# adc.net
KiCad netlist of a schematic drawn in Altium Designer
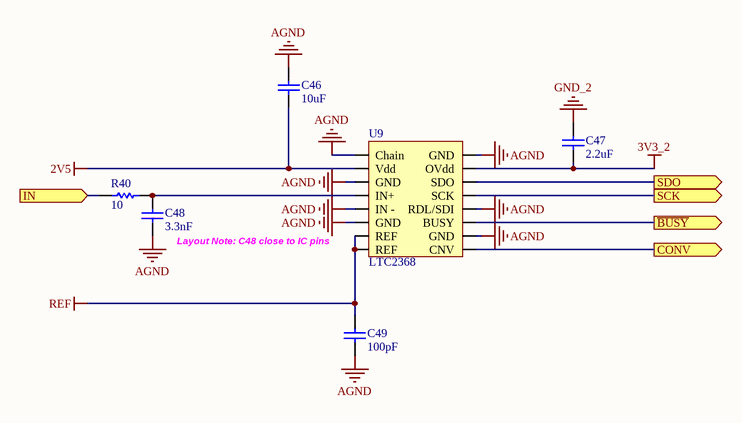
[diagram p0: adc.SchDoc]

(export (version "E")
  (design (tool "Eeschema 10.0.6"))
  (components
    (comp (ref "C46")
      (value "10uF")
      (footprint "0402_Cap")
      (description "Capacitor, 10uF, 0805")
      (libsource (lib "Arturo_Approved") (part "CL21A106KAFN3NE"))
    )
    (comp (ref "C47")
      (value "2.2uF")
      (footprint "0402_Cap")
      (description "Capacitor, 2.2uF, 0805")
      (libsource (lib "Arturo_Approved") (part "CL21A225KAFNNNE"))
    )
    (comp (ref "C48")
      (value "3.3nF")
      (footprint "0402_Cap")
      (description "Capacitor, 3.3nF, 0805")
      (libsource (lib "Arturo_Approved") (part "C0805C332KARACAUTO"))
    )
    (comp (ref "C49")
      (value "100pF")
      (footprint "STD_0805_C")
      (description "Capacitor, 100pF, 0805")
      (libsource (lib "Arturo_Approved") (part "CL21C101JCANNNC"))
    )
    (comp (ref "R40")
      (value "10")
      (footprint "0402_Res")
      (description "10 ohm 0805")
      (libsource (lib "Arturo_Approved") (part "RNCF0805DTE10R0"))
    )
    (comp (ref "U9")
      (value "LTC2368")
      (footprint "MSOP_16")
      (libsource (lib "Arturo_Approved") (part "LTC2368"))
    )
  )
  (nets
    (net (code "1") (name "/CONV") (class "Default")
      (node (ref "U9") (pin "9") (pinfunction "CNV_9") (pintype "passive"))
    )
    (net (code "2") (name "/IN") (class "Default")
      (node (ref "R40") (pin "1") (pinfunction "1_1") (pintype "passive"))
    )
    (net (code "3") (name "/SCK") (class "Default")
      (node (ref "U9") (pin "13") (pinfunction "SCK_13") (pintype "passive"))
    )
    (net (code "4") (name "/SDO") (class "Default")
      (node (ref "U9") (pin "14") (pinfunction "SDO_14") (pintype "passive"))
    )
    (net (code "5") (name "/~{BUSY}") (class "Default")
      (node (ref "U9") (pin "11") (pinfunction "BUSY_11") (pintype "passive"))
    )
    (net (code "6") (name "2V5") (class "Default")
      (node (ref "C46") (pin "1") (pinfunction "1_1") (pintype "passive"))
      (node (ref "U9") (pin "2") (pinfunction "Vdd_2") (pintype "passive"))
    )
    (net (code "7") (name "3V3_2") (class "Default")
      (node (ref "C47") (pin "1") (pinfunction "1_1") (pintype "passive"))
      (node (ref "U9") (pin "15") (pinfunction "OVdd_15") (pintype "passive"))
    )
    (net (code "8") (name "AGND") (class "Default")
      (node (ref "C46") (pin "2") (pinfunction "2_2") (pintype "passive"))
      (node (ref "C48") (pin "1") (pinfunction "1_1") (pintype "passive"))
      (node (ref "C49") (pin "1") (pinfunction "1_1") (pintype "passive"))
      (node (ref "U9") (pin "1") (pinfunction "Chain_1") (pintype "passive"))
      (node (ref "U9") (pin "10") (pinfunction "GND_10") (pintype "passive"))
      (node (ref "U9") (pin "12") (pinfunction "RDL/SDI_12") (pintype "passive"))
      (node (ref "U9") (pin "16") (pinfunction "GND_16") (pintype "passive"))
      (node (ref "U9") (pin "3") (pinfunction "GND_3") (pintype "passive"))
      (node (ref "U9") (pin "5") (pinfunction "IN_-_5") (pintype "passive"))
      (node (ref "U9") (pin "6") (pinfunction "GND_6") (pintype "passive"))
    )
    (net (code "9") (name "GND_2") (class "Default")
      (node (ref "C47") (pin "2") (pinfunction "2_2") (pintype "passive"))
    )
    (net (code "10") (name "Net-(U9-IN+)") (class "Default")
      (node (ref "C48") (pin "2") (pinfunction "2_2") (pintype "passive"))
      (node (ref "R40") (pin "2") (pinfunction "2_2") (pintype "passive"))
      (node (ref "U9") (pin "4") (pinfunction "IN+_4") (pintype "passive"))
    )
    (net (code "11") (name "REF") (class "Default")
      (node (ref "C49") (pin "2") (pinfunction "2_2") (pintype "passive"))
      (node (ref "U9") (pin "7") (pinfunction "REF_7") (pintype "passive"))
      (node (ref "U9") (pin "8") (pinfunction "REF_8") (pintype "passive"))
    )
  )
)
